# NOT_Gate.net
KiCad netlist of a schematic drawn in EAGLE
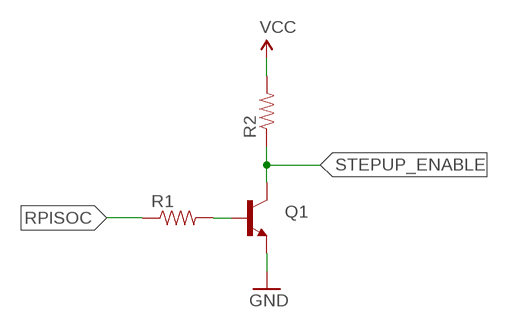
[diagram p0: schematic, sheet 1]

(export (version "E")
  (design (tool "Eeschema 10.0.6"))
  (components
    (comp (ref "Q1")
      (value "TRANSISTOR_NPN2N3904")
      (footprint "eagle-import:TO-92")
      (libsource (lib "eagle-import") (part "TRANSISTOR_NPN2N3904"))
    )
    (comp (ref "R1")
      (value "RESISTOR0603")
      (footprint "eagle-import:0603-RES")
      (libsource (lib "eagle-import") (part "RESISTOR0603"))
    )
    (comp (ref "R2")
      (value "RESISTOR0603")
      (footprint "eagle-import:0603-RES")
      (libsource (lib "eagle-import") (part "RESISTOR0603"))
    )
  )
  (nets
    (net (code "1") (name "GND") (class "Default")
      (node (ref "Q1") (pin "1") (pinfunction "E_1") (pintype "passive"))
    )
    (net (code "2") (name "Net-(Q1-B)") (class "Default")
      (node (ref "Q1") (pin "2") (pinfunction "B_2") (pintype "passive"))
      (node (ref "R1") (pin "2") (pinfunction "2_2") (pintype "passive"))
    )
    (net (code "3") (name "RPISOC") (class "Default")
      (node (ref "R1") (pin "1") (pinfunction "1_1") (pintype "passive"))
    )
    (net (code "4") (name "STEPUP_ENABLE") (class "Default")
      (node (ref "Q1") (pin "3") (pinfunction "C_3") (pintype "passive"))
      (node (ref "R2") (pin "1") (pinfunction "1_1") (pintype "passive"))
    )
    (net (code "5") (name "VCC") (class "Default")
      (node (ref "R2") (pin "2") (pinfunction "2_2") (pintype "passive"))
    )
  )
)
